# PDB2.net
KiCad netlist of a schematic drawn in EAGLE
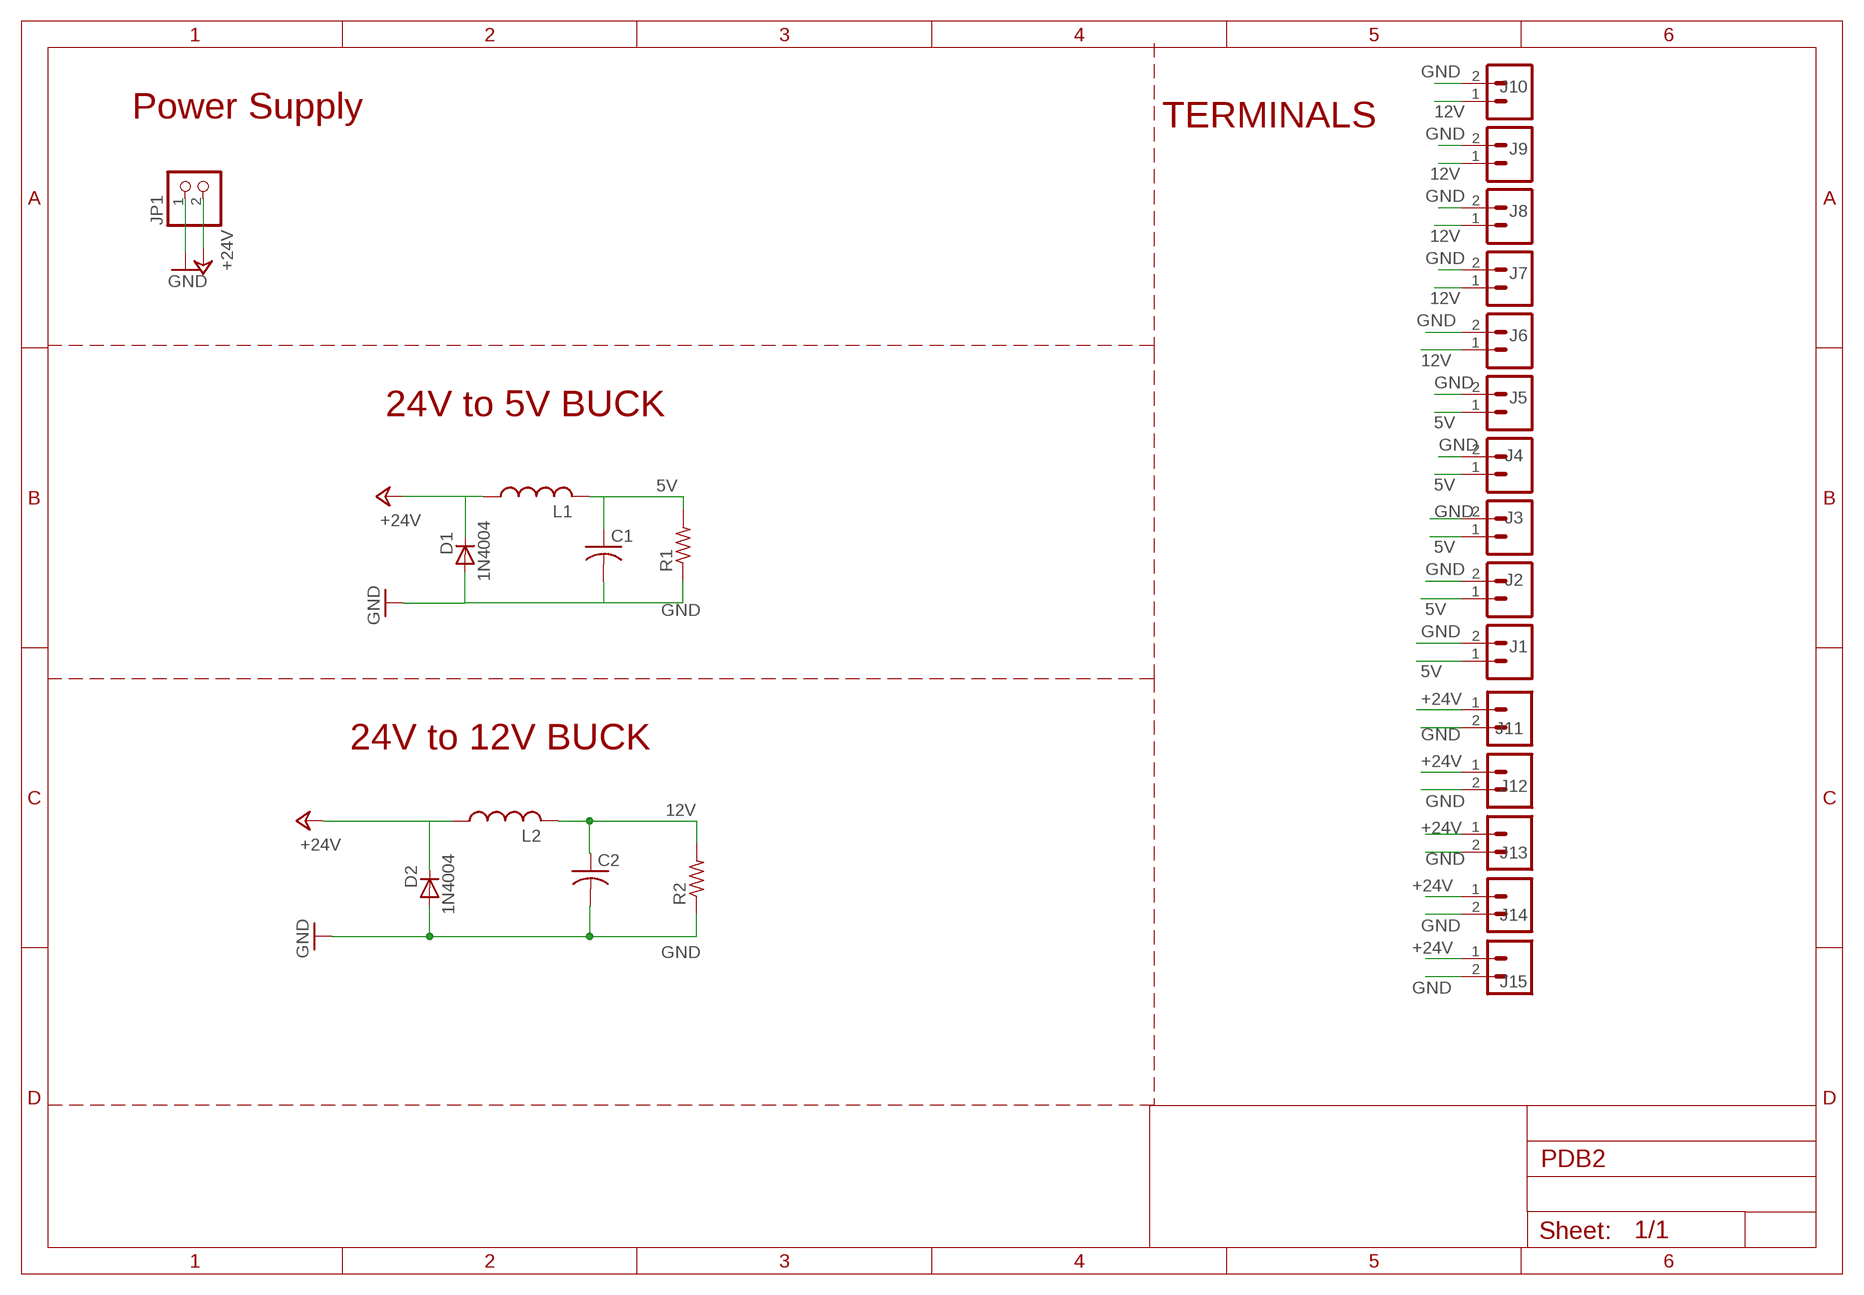
[diagram p0: schematic, sheet 1]

(export (version "E")
  (design (tool "Eeschema 10.0.6"))
  (components
    (comp (ref "C1")
      (value "C-US025-050X050")
      (footprint "eagle-import:C025-050X050")
      (libsource (lib "eagle-import") (part "C-US025-050X050"))
    )
    (comp (ref "C2")
      (value "C-US025-050X050")
      (footprint "eagle-import:C025-050X050")
      (libsource (lib "eagle-import") (part "C-US025-050X050"))
    )
    (comp (ref "D1")
      (value "1N4004")
      (footprint "eagle-import:DO41-10")
      (libsource (lib "eagle-import") (part "1N4004"))
    )
    (comp (ref "D2")
      (value "1N4004")
      (footprint "eagle-import:DO41-10")
      (libsource (lib "eagle-import") (part "1N4004"))
    )
    (comp (ref "J1")
      (value "CONN_02")
      (footprint "eagle-import:1X02")
      (libsource (lib "eagle-import") (part "CONN_02"))
    )
    (comp (ref "J2")
      (value "CONN_02")
      (footprint "eagle-import:1X02")
      (libsource (lib "eagle-import") (part "CONN_02"))
    )
    (comp (ref "J3")
      (value "CONN_02")
      (footprint "eagle-import:1X02")
      (libsource (lib "eagle-import") (part "CONN_02"))
    )
    (comp (ref "J4")
      (value "CONN_02")
      (footprint "eagle-import:1X02")
      (libsource (lib "eagle-import") (part "CONN_02"))
    )
    (comp (ref "J5")
      (value "CONN_02")
      (footprint "eagle-import:1X02")
      (libsource (lib "eagle-import") (part "CONN_02"))
    )
    (comp (ref "J6")
      (value "CONN_02")
      (footprint "eagle-import:1X02")
      (libsource (lib "eagle-import") (part "CONN_02"))
    )
    (comp (ref "J7")
      (value "CONN_02")
      (footprint "eagle-import:1X02")
      (libsource (lib "eagle-import") (part "CONN_02"))
    )
    (comp (ref "J8")
      (value "CONN_02")
      (footprint "eagle-import:1X02")
      (libsource (lib "eagle-import") (part "CONN_02"))
    )
    (comp (ref "J9")
      (value "CONN_02")
      (footprint "eagle-import:1X02")
      (libsource (lib "eagle-import") (part "CONN_02"))
    )
    (comp (ref "J10")
      (value "CONN_02")
      (footprint "eagle-import:1X02")
      (libsource (lib "eagle-import") (part "CONN_02"))
    )
    (comp (ref "J11")
      (value "CONN_02")
      (footprint "eagle-import:1X02")
      (libsource (lib "eagle-import") (part "CONN_02"))
    )
    (comp (ref "J12")
      (value "CONN_02")
      (footprint "eagle-import:1X02")
      (libsource (lib "eagle-import") (part "CONN_02"))
    )
    (comp (ref "J13")
      (value "CONN_02")
      (footprint "eagle-import:1X02")
      (libsource (lib "eagle-import") (part "CONN_02"))
    )
    (comp (ref "J14")
      (value "CONN_02")
      (footprint "eagle-import:1X02")
      (libsource (lib "eagle-import") (part "CONN_02"))
    )
    (comp (ref "J15")
      (value "CONN_02")
      (footprint "eagle-import:1X02")
      (libsource (lib "eagle-import") (part "CONN_02"))
    )
    (comp (ref "JP1")
      (value "PINHD-1X2")
      (footprint "eagle-import:1X02")
      (libsource (lib "eagle-import") (part "PINHD-1X2"))
    )
    (comp (ref "L1")
      (value "L-US0207/7")
      (footprint "eagle-import:0207_7")
      (libsource (lib "eagle-import") (part "L-US0207/7"))
    )
    (comp (ref "L2")
      (value "L-US0207/7")
      (footprint "eagle-import:0207_7")
      (libsource (lib "eagle-import") (part "L-US0207/7"))
    )
    (comp (ref "R1")
      (value "R-US_0207/10")
      (footprint "eagle-import:0207_10")
      (libsource (lib "eagle-import") (part "R-US_0207/10"))
    )
    (comp (ref "R2")
      (value "R-US_0207/10")
      (footprint "eagle-import:0207_10")
      (libsource (lib "eagle-import") (part "R-US_0207/10"))
    )
  )
  (nets
    (net (code "1") (name "+24V") (class "Default")
      (node (ref "D1") (pin "C") (pinfunction "C_C") (pintype "passive"))
      (node (ref "D2") (pin "C") (pinfunction "C_C") (pintype "passive"))
      (node (ref "J11") (pin "1") (pinfunction "1_1") (pintype "passive"))
      (node (ref "J12") (pin "1") (pinfunction "1_1") (pintype "passive"))
      (node (ref "J13") (pin "1") (pinfunction "1_1") (pintype "passive"))
      (node (ref "J14") (pin "1") (pinfunction "1_1") (pintype "passive"))
      (node (ref "J15") (pin "1") (pinfunction "1_1") (pintype "passive"))
      (node (ref "JP1") (pin "2") (pinfunction "2_2") (pintype "passive"))
      (node (ref "L1") (pin "1") (pinfunction "1_1") (pintype "passive"))
      (node (ref "L2") (pin "1") (pinfunction "1_1") (pintype "passive"))
    )
    (net (code "2") (name "/5V") (class "Default")
      (node (ref "C1") (pin "1") (pinfunction "1_1") (pintype "passive"))
      (node (ref "J1") (pin "1") (pinfunction "1_1") (pintype "passive"))
      (node (ref "J2") (pin "1") (pinfunction "1_1") (pintype "passive"))
      (node (ref "J3") (pin "1") (pinfunction "1_1") (pintype "passive"))
      (node (ref "J4") (pin "1") (pinfunction "1_1") (pintype "passive"))
      (node (ref "J5") (pin "1") (pinfunction "1_1") (pintype "passive"))
      (node (ref "L1") (pin "2") (pinfunction "2_2") (pintype "passive"))
      (node (ref "R1") (pin "2") (pinfunction "2_2") (pintype "passive"))
    )
    (net (code "3") (name "/12V") (class "Default")
      (node (ref "C2") (pin "1") (pinfunction "1_1") (pintype "passive"))
      (node (ref "J10") (pin "1") (pinfunction "1_1") (pintype "passive"))
      (node (ref "J6") (pin "1") (pinfunction "1_1") (pintype "passive"))
      (node (ref "J7") (pin "1") (pinfunction "1_1") (pintype "passive"))
      (node (ref "J8") (pin "1") (pinfunction "1_1") (pintype "passive"))
      (node (ref "J9") (pin "1") (pinfunction "1_1") (pintype "passive"))
      (node (ref "L2") (pin "2") (pinfunction "2_2") (pintype "passive"))
      (node (ref "R2") (pin "2") (pinfunction "2_2") (pintype "passive"))
    )
    (net (code "4") (name "GND") (class "Default")
      (node (ref "C1") (pin "2") (pinfunction "2_2") (pintype "passive"))
      (node (ref "C2") (pin "2") (pinfunction "2_2") (pintype "passive"))
      (node (ref "D1") (pin "A") (pinfunction "A_A") (pintype "passive"))
      (node (ref "D2") (pin "A") (pinfunction "A_A") (pintype "passive"))
      (node (ref "J1") (pin "2") (pinfunction "2_2") (pintype "passive"))
      (node (ref "J10") (pin "2") (pinfunction "2_2") (pintype "passive"))
      (node (ref "J11") (pin "2") (pinfunction "2_2") (pintype "passive"))
      (node (ref "J12") (pin "2") (pinfunction "2_2") (pintype "passive"))
      (node (ref "J13") (pin "2") (pinfunction "2_2") (pintype "passive"))
      (node (ref "J14") (pin "2") (pinfunction "2_2") (pintype "passive"))
      (node (ref "J15") (pin "2") (pinfunction "2_2") (pintype "passive"))
      (node (ref "J2") (pin "2") (pinfunction "2_2") (pintype "passive"))
      (node (ref "J3") (pin "2") (pinfunction "2_2") (pintype "passive"))
      (node (ref "J4") (pin "2") (pinfunction "2_2") (pintype "passive"))
      (node (ref "J5") (pin "2") (pinfunction "2_2") (pintype "passive"))
      (node (ref "J6") (pin "2") (pinfunction "2_2") (pintype "passive"))
      (node (ref "J7") (pin "2") (pinfunction "2_2") (pintype "passive"))
      (node (ref "J8") (pin "2") (pinfunction "2_2") (pintype "passive"))
      (node (ref "J9") (pin "2") (pinfunction "2_2") (pintype "passive"))
      (node (ref "JP1") (pin "1") (pinfunction "1_1") (pintype "passive"))
      (node (ref "R1") (pin "1") (pinfunction "1_1") (pintype "passive"))
      (node (ref "R2") (pin "1") (pinfunction "1_1") (pintype "passive"))
    )
  )
)
